# CAN-to-CAN.net
KiCad netlist of a schematic drawn in Altium Designer
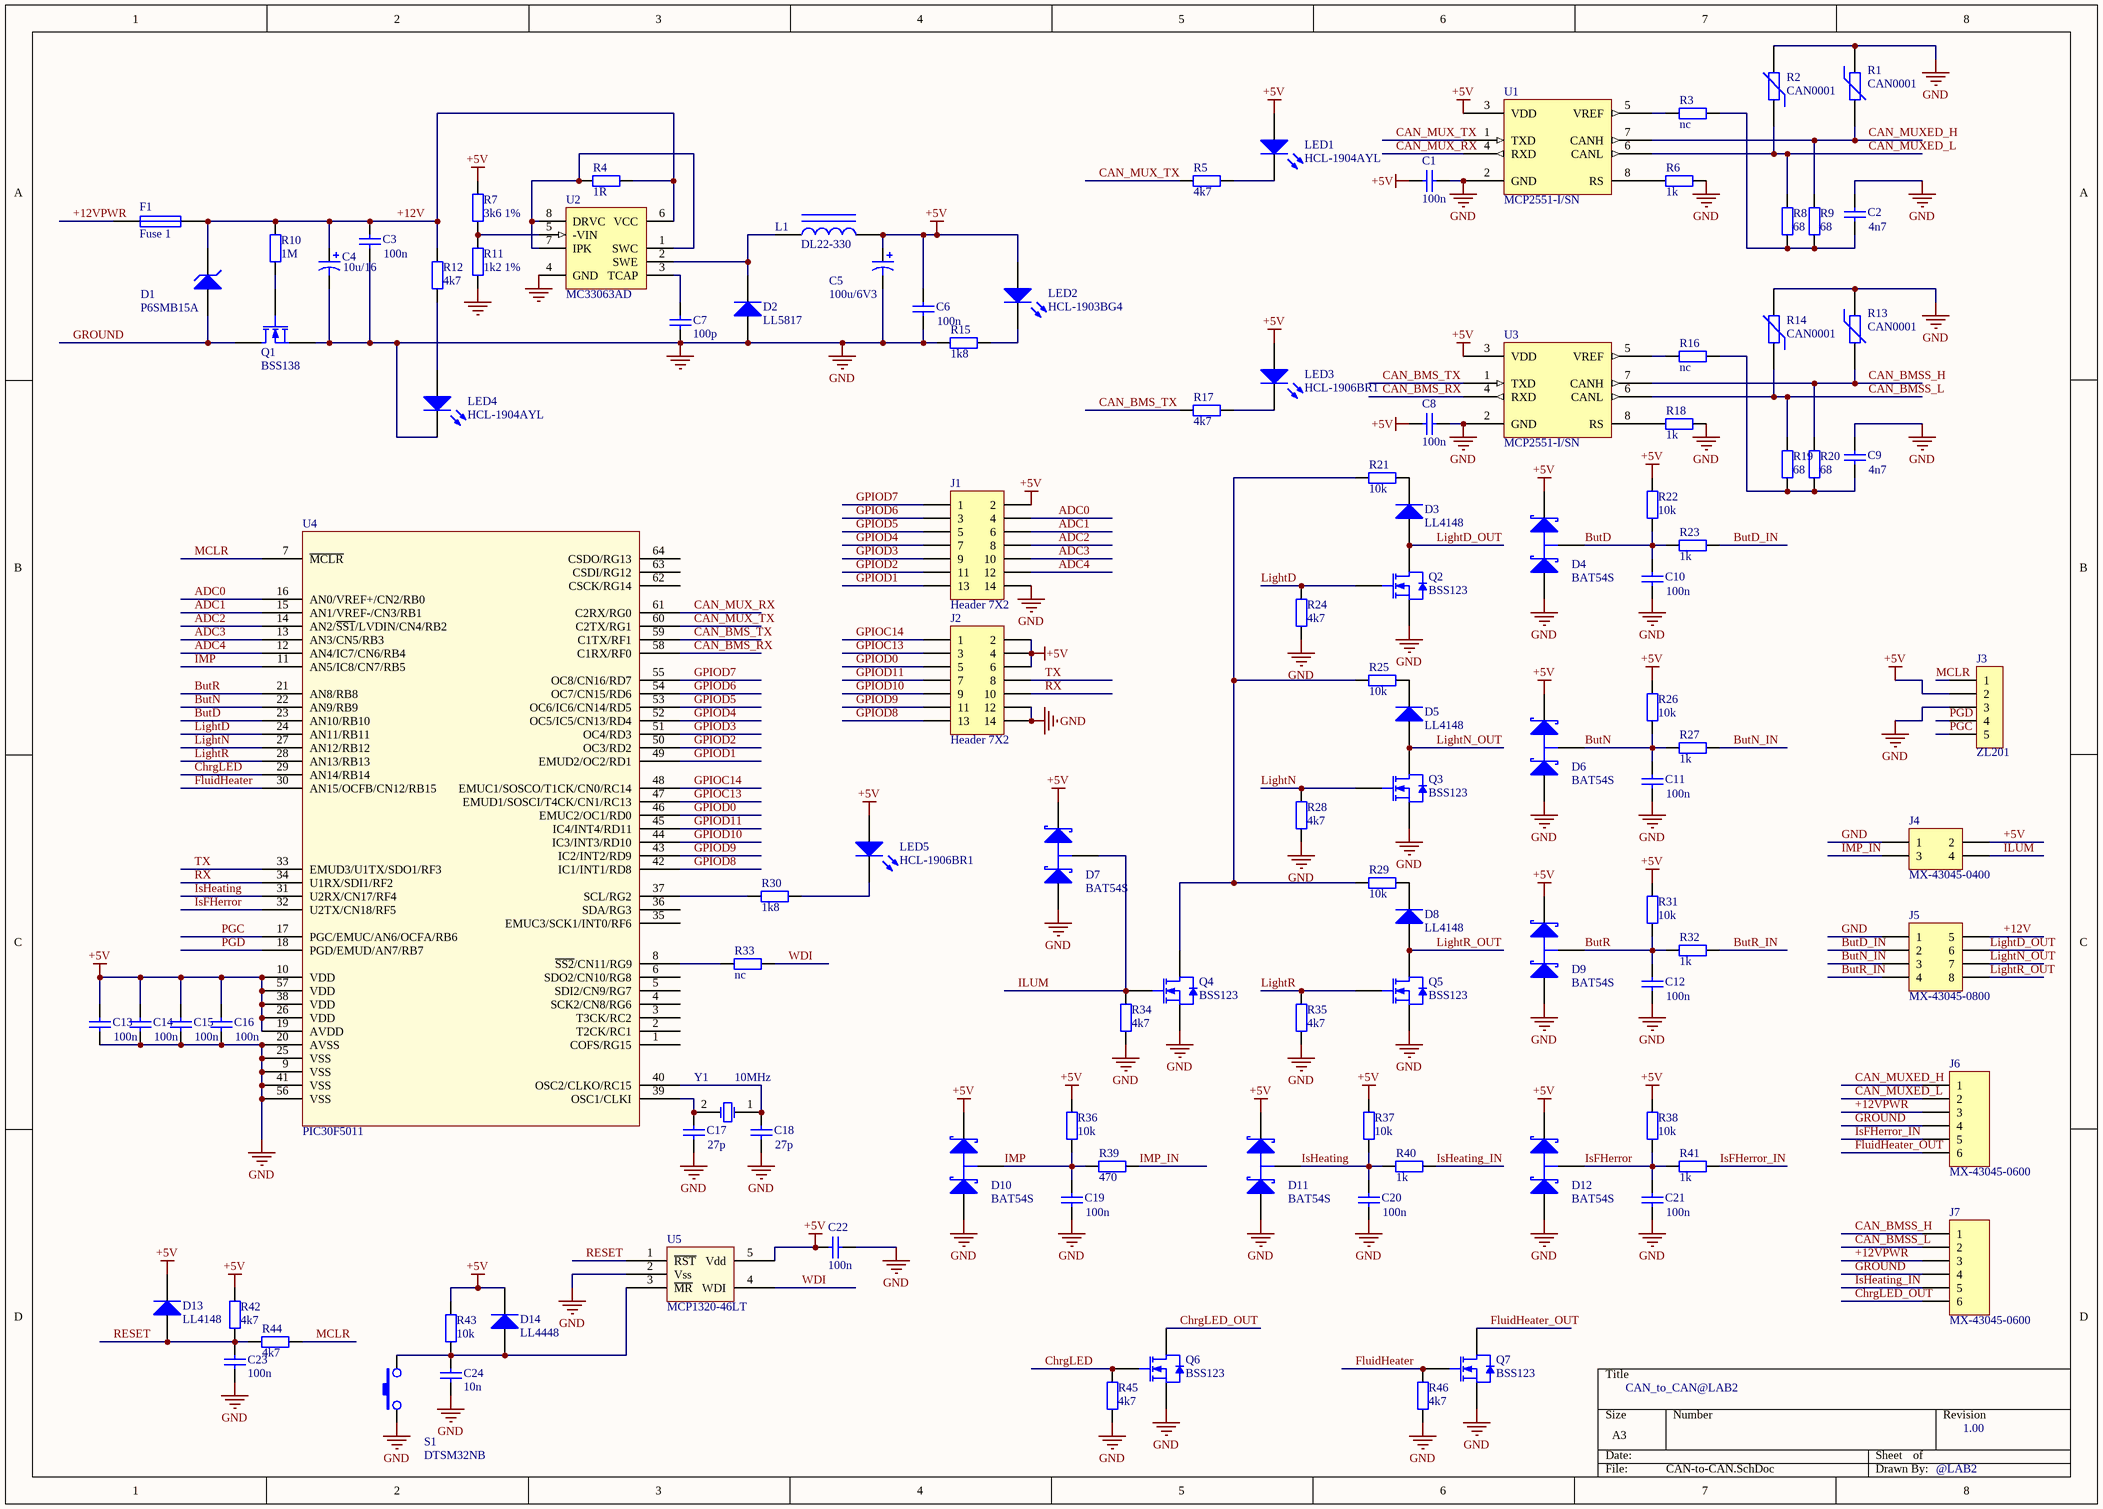
[diagram p0: CAN-to-CAN.SchDoc]

(export (version "E")
  (design (tool "Eeschema 10.0.6"))
  (components
    (comp (ref "C1")
      (value "100n")
      (footprint "0603")
      (description "Capacitor")
      (libsource (lib "Miscellaneous Devices") (part "Cap"))
    )
    (comp (ref "C2")
      (value "4n7")
      (footprint "0603")
      (description "Capacitor")
      (libsource (lib "Miscellaneous Devices") (part "Cap"))
    )
    (comp (ref "C3")
      (value "100n")
      (footprint "3.2X1.6X1.1")
      (description "Capacitor")
      (libsource (lib "Miscellaneous Devices") (part "Cap"))
    )
    (comp (ref "C4")
      (value "10u/16")
      (footprint "1608[0603]")
      (description "Polarized Capacitor (Radial)")
      (libsource (lib "Miscellaneous Devices") (part "Cap Pol1"))
    )
    (comp (ref "C5")
      (value "100u/6V3")
      (footprint "0402")
      (description "Polarized Capacitor (Radial)")
      (libsource (lib "Miscellaneous Devices") (part "Cap Pol1"))
    )
    (comp (ref "C6")
      (value "100n")
      (footprint "0603")
      (description "Capacitor")
      (libsource (lib "Miscellaneous Devices") (part "Cap"))
    )
    (comp (ref "C7")
      (value "100p")
      (footprint "0603")
      (description "Capacitor")
      (libsource (lib "Miscellaneous Devices") (part "Cap"))
    )
    (comp (ref "C8")
      (value "100n")
      (footprint "0603")
      (description "Capacitor")
      (libsource (lib "Miscellaneous Devices") (part "Cap"))
    )
    (comp (ref "C9")
      (value "4n7")
      (footprint "0603")
      (description "Capacitor")
      (libsource (lib "Miscellaneous Devices") (part "Cap"))
    )
    (comp (ref "C10")
      (value "100n")
      (footprint "0603")
      (description "Capacitor")
      (libsource (lib "Miscellaneous Devices") (part "Cap"))
    )
    (comp (ref "C11")
      (value "100n")
      (footprint "0603")
      (description "Capacitor")
      (libsource (lib "Miscellaneous Devices") (part "Cap"))
    )
    (comp (ref "C12")
      (value "100n")
      (footprint "0603")
      (description "Capacitor")
      (libsource (lib "Miscellaneous Devices") (part "Cap"))
    )
    (comp (ref "C13")
      (value "100n")
      (footprint "0603")
      (description "Capacitor")
      (libsource (lib "Miscellaneous Devices") (part "Cap"))
    )
    (comp (ref "C14")
      (value "100n")
      (footprint "0603")
      (description "Capacitor")
      (libsource (lib "Miscellaneous Devices") (part "Cap"))
    )
    (comp (ref "C15")
      (value "100n")
      (footprint "0603")
      (description "Capacitor")
      (libsource (lib "Miscellaneous Devices") (part "Cap"))
    )
    (comp (ref "C16")
      (value "100n")
      (footprint "0603")
      (description "Capacitor")
      (libsource (lib "Miscellaneous Devices") (part "Cap"))
    )
    (comp (ref "C17")
      (value "27p")
      (footprint "0603")
      (description "Capacitor")
      (libsource (lib "Miscellaneous Devices") (part "Cap"))
    )
    (comp (ref "C18")
      (value "27p")
      (footprint "0603")
      (description "Capacitor")
      (libsource (lib "Miscellaneous Devices") (part "Cap"))
    )
    (comp (ref "C19")
      (value "100n")
      (footprint "0603")
      (description "Capacitor")
      (libsource (lib "Miscellaneous Devices") (part "Cap"))
    )
    (comp (ref "C20")
      (value "100n")
      (footprint "0603")
      (description "Capacitor")
      (libsource (lib "Miscellaneous Devices") (part "Cap"))
    )
    (comp (ref "C21")
      (value "100n")
      (footprint "0603")
      (description "Capacitor")
      (libsource (lib "Miscellaneous Devices") (part "Cap"))
    )
    (comp (ref "C22")
      (value "100n")
      (footprint "0603")
      (description "Capacitor")
      (libsource (lib "Miscellaneous Devices") (part "Cap"))
    )
    (comp (ref "C23")
      (value "100n")
      (footprint "0603")
      (description "Capacitor")
      (libsource (lib "Miscellaneous Devices") (part "Cap"))
    )
    (comp (ref "C24")
      (value "10n")
      (footprint "0603")
      (description "Capacitor")
      (libsource (lib "Miscellaneous Devices") (part "Cap"))
    )
    (comp (ref "D1")
      (value "P6SMB15A")
      (footprint "SMB")
      (description "Zener Diode")
      (libsource (lib "Miscellaneous Devices") (part "D Zener"))
    )
    (comp (ref "D2")
      (value "LL5817")
      (footprint "3.2X1.6X1.1")
      (description "High Conductance Fast Diode")
      (libsource (lib "FSC Discrete Diode") (part "1N4148"))
    )
    (comp (ref "D3")
      (value "LL4148")
      (footprint "3.2X1.6X1.1")
      (description "High Conductance Fast Diode")
      (libsource (lib "FSC Discrete Diode") (part "1N4148"))
    )
    (comp (ref "D4")
      (value "BAT54S")
      (footprint "3.2X1.6X1.1")
      (description "Schottky Barrier Double Diode")
      (libsource (lib "Philips Discrete Diode - Schottky") (part "BAT54S"))
    )
    (comp (ref "D5")
      (value "LL4148")
      (footprint "3.2X1.6X1.1")
      (description "High Conductance Fast Diode")
      (libsource (lib "FSC Discrete Diode") (part "1N4148"))
    )
    (comp (ref "D6")
      (value "BAT54S")
      (footprint "3.5X2.8X1.9")
      (description "Schottky Barrier Double Diode")
      (libsource (lib "Philips Discrete Diode - Schottky") (part "BAT54S"))
    )
    (comp (ref "D7")
      (value "BAT54S")
      (footprint "3.2X1.6X1.1")
      (description "Schottky Barrier Double Diode")
      (libsource (lib "Philips Discrete Diode - Schottky") (part "BAT54S"))
    )
    (comp (ref "D8")
      (value "LL4148")
      (footprint "3.2X1.6X1.1")
      (description "High Conductance Fast Diode")
      (libsource (lib "FSC Discrete Diode") (part "1N4148"))
    )
    (comp (ref "D9")
      (value "BAT54S")
      (footprint "3.5X2.8X1.9")
      (description "Schottky Barrier Double Diode")
      (libsource (lib "Philips Discrete Diode - Schottky") (part "BAT54S"))
    )
    (comp (ref "D10")
      (value "BAT54S")
      (footprint "3.2X1.6X1.1")
      (description "Schottky Barrier Double Diode")
      (libsource (lib "Philips Discrete Diode - Schottky") (part "BAT54S"))
    )
    (comp (ref "D11")
      (value "BAT54S")
      (footprint "3.2X1.6X1.1")
      (description "Schottky Barrier Double Diode")
      (libsource (lib "Philips Discrete Diode - Schottky") (part "BAT54S"))
    )
    (comp (ref "D12")
      (value "BAT54S")
      (footprint "3.2X1.6X1.1")
      (description "Schottky Barrier Double Diode")
      (libsource (lib "Philips Discrete Diode - Schottky") (part "BAT54S"))
    )
    (comp (ref "D13")
      (value "LL4148")
      (footprint "3.2X1.6X1.1")
      (description "High Conductance Fast Diode")
      (libsource (lib "FSC Discrete Diode") (part "1N4148"))
    )
    (comp (ref "D14")
      (value "LL4448")
      (footprint "3.2X1.6X1.1")
      (description "Default Diode")
      (libsource (lib "Miscellaneous Devices") (part "Diode"))
    )
    (comp (ref "F1")
      (value "Fuse 1")
      (footprint "1812")
      (description "Fuse")
      (libsource (lib "Miscellaneous Devices") (part "Fuse 1"))
    )
    (comp (ref "J1")
      (value "Header 7X2")
      (footprint "HDR2X7")
      (description "Header, 7-Pin, Dual row")
      (libsource (lib "Miscellaneous Connectors") (part "Header 7X2"))
    )
    (comp (ref "J2")
      (value "Header 7X2")
      (footprint "HDR2X7")
      (description "Header, 7-Pin, Dual row")
      (libsource (lib "Miscellaneous Connectors") (part "Header 7X2"))
    )
    (comp (ref "J3")
      (value "ZL201")
      (footprint "HDR1X5")
      (description "Connector")
      (libsource (lib "*") (part "CON5"))
    )
    (comp (ref "J4")
      (value "MX-43045-0400")
      (footprint "MHDR2X2")
      (description "Header, 2-Pin, Dual row")
      (libsource (lib "Miscellaneous Connectors") (part "Header 2X2"))
    )
    (comp (ref "J5")
      (value "MX-43045-0800")
      (footprint "MHDR2X8")
      (description "Header, 4-Pin, Dual row")
      (libsource (lib "Miscellaneous Connectors") (part "Header 4X2A"))
    )
    (comp (ref "J6")
      (value "MX-43045-0600")
      (footprint "MHDR1X6")
      (description "Header, 6-Pin")
      (libsource (lib "Miscellaneous Connectors") (part "Header 6"))
    )
    (comp (ref "J7")
      (value "MX-43045-0600")
      (footprint "MHDR1X6")
      (description "Header, 6-Pin")
      (libsource (lib "Miscellaneous Connectors") (part "Header 6"))
    )
    (comp (ref "L1")
      (value "DL22-330")
      (footprint "14-1210")
      (description "Magnetic-Core Inductor")
      (libsource (lib "Miscellaneous Devices") (part "Inductor Iron"))
    )
    (comp (ref "LED1")
      (value "HCL-1904AYL")
      (footprint "0603")
      (description "Typical BLUE SiC LED")
      (libsource (lib "Miscellaneous Devices") (part "LED3"))
    )
    (comp (ref "LED2")
      (value "HCL-1903BG4")
      (footprint "0603")
      (description "Typical BLUE SiC LED")
      (libsource (lib "Miscellaneous Devices") (part "LED3"))
    )
    (comp (ref "LED3")
      (value "HCL-1906BR1")
      (footprint "0603")
      (description "Typical BLUE SiC LED")
      (libsource (lib "Miscellaneous Devices") (part "LED3"))
    )
    (comp (ref "LED4")
      (value "HCL-1904AYL")
      (footprint "0603")
      (description "Typical BLUE SiC LED")
      (libsource (lib "Miscellaneous Devices") (part "LED3"))
    )
    (comp (ref "LED5")
      (value "HCL-1906BR1")
      (footprint "0603")
      (description "Typical BLUE SiC LED")
      (libsource (lib "Miscellaneous Devices") (part "LED3"))
    )
    (comp (ref "Q1")
      (value "BSS138")
      (footprint "3.2X1.6X1.1")
      (description "N-Channel Enhancement Mode Vertical DMOS FET")
      (libsource (lib "Zetex Discrete MOSFET") (part "BSS138"))
    )
    (comp (ref "Q2")
      (value "BSS123")
      (footprint "3.2X1.6X1.1")
      (description "N-channel Enhancement Mode Vertical D-MOSFET")
      (libsource (lib "Philips Discrete MOSFET - Low Power") (part "BSS123"))
    )
    (comp (ref "Q3")
      (value "BSS123")
      (footprint "3.2X1.6X1.1")
      (description "N-channel Enhancement Mode Vertical D-MOSFET")
      (libsource (lib "Philips Discrete MOSFET - Low Power") (part "BSS123"))
    )
    (comp (ref "Q4")
      (value "BSS123")
      (footprint "3.5X2.8X1.9")
      (description "N-channel Enhancement Mode Vertical D-MOSFET")
      (libsource (lib "Philips Discrete MOSFET - Low Power") (part "BSS123"))
    )
    (comp (ref "Q5")
      (value "BSS123")
      (footprint "3.5X2.8X1.9")
      (description "N-channel Enhancement Mode Vertical D-MOSFET")
      (libsource (lib "Philips Discrete MOSFET - Low Power") (part "BSS123"))
    )
    (comp (ref "Q6")
      (value "BSS123")
      (footprint "3.2X1.6X1.1")
      (description "N-channel Enhancement Mode Vertical D-MOSFET")
      (libsource (lib "Philips Discrete MOSFET - Low Power") (part "BSS123"))
    )
    (comp (ref "Q7")
      (value "BSS123")
      (footprint "3.5X2.8X1.9")
      (description "N-channel Enhancement Mode Vertical D-MOSFET")
      (libsource (lib "Philips Discrete MOSFET - Low Power") (part "BSS123"))
    )
    (comp (ref "R1")
      (value "CAN0001")
      (footprint "0603")
      (description "Varistor (Voltage-Sensitive Resistor)")
      (libsource (lib "Miscellaneous Devices") (part "Res Varistor"))
    )
    (comp (ref "R2")
      (value "CAN0001")
      (footprint "0603")
      (description "Varistor (Voltage-Sensitive Resistor)")
      (libsource (lib "Miscellaneous Devices") (part "Res Varistor"))
    )
    (comp (ref "R3")
      (value "nc")
      (footprint "0603")
      (description "Resistor")
      (libsource (lib "") (part "Res2_2"))
    )
    (comp (ref "R4")
      (value "1R")
      (footprint "RESC6332")
      (description "Resistor")
      (libsource (lib "") (part "Res2_2"))
    )
    (comp (ref "R5")
      (value "4k7")
      (footprint "0603")
      (description "Resistor")
      (libsource (lib "") (part "Res2_1"))
    )
    (comp (ref "R6")
      (value "1k")
      (footprint "0603")
      (description "Resistor")
      (libsource (lib "") (part "Res2_2"))
    )
    (comp (ref "R7")
      (value "3k6 1%")
      (footprint "0603")
      (description "Resistor")
      (libsource (lib "Miscellaneous Devices") (part "Res2"))
    )
    (comp (ref "R8")
      (value "68")
      (footprint "0603")
      (description "Resistor")
      (libsource (lib "Miscellaneous Devices") (part "Res2"))
    )
    (comp (ref "R9")
      (value "68")
      (footprint "0603")
      (description "Resistor")
      (libsource (lib "Miscellaneous Devices") (part "Res2"))
    )
    (comp (ref "R10")
      (value "1M")
      (footprint "0603")
      (description "Resistor")
      (libsource (lib "Miscellaneous Devices") (part "Res2"))
    )
    (comp (ref "R11")
      (value "1k2 1%")
      (footprint "0603")
      (description "Resistor")
      (libsource (lib "") (part "Res2_3"))
    )
    (comp (ref "R12")
      (value "4k7")
      (footprint "0603")
      (description "Resistor")
      (libsource (lib "Miscellaneous Devices") (part "Res2"))
    )
    (comp (ref "R13")
      (value "CAN0001")
      (footprint "0603")
      (description "Varistor (Voltage-Sensitive Resistor)")
      (libsource (lib "Miscellaneous Devices") (part "Res Varistor"))
    )
    (comp (ref "R14")
      (value "CAN0001")
      (footprint "0603")
      (description "Varistor (Voltage-Sensitive Resistor)")
      (libsource (lib "Miscellaneous Devices") (part "Res Varistor"))
    )
    (comp (ref "R15")
      (value "1k8")
      (footprint "0603")
      (description "Resistor")
      (libsource (lib "") (part "Res2_1"))
    )
    (comp (ref "R16")
      (value "nc")
      (footprint "0603")
      (description "Resistor")
      (libsource (lib "") (part "Res2_2"))
    )
    (comp (ref "R17")
      (value "4k7")
      (footprint "0603")
      (description "Resistor")
      (libsource (lib "") (part "Res2_1"))
    )
    (comp (ref "R18")
      (value "1k")
      (footprint "0603")
      (description "Resistor")
      (libsource (lib "") (part "Res2_2"))
    )
    (comp (ref "R19")
      (value "68")
      (footprint "0603")
      (description "Resistor")
      (libsource (lib "Miscellaneous Devices") (part "Res2"))
    )
    (comp (ref "R20")
      (value "68")
      (footprint "0603")
      (description "Resistor")
      (libsource (lib "Miscellaneous Devices") (part "Res2"))
    )
    (comp (ref "R21")
      (value "10k")
      (footprint "0603")
      (description "Resistor")
      (libsource (lib "") (part "Res2_2"))
    )
    (comp (ref "R22")
      (value "10k")
      (footprint "0603")
      (description "Resistor")
      (libsource (lib "Miscellaneous Devices") (part "Res2"))
    )
    (comp (ref "R23")
      (value "1k")
      (footprint "0603")
      (description "Resistor")
      (libsource (lib "") (part "Res2_1"))
    )
    (comp (ref "R24")
      (value "4k7")
      (footprint "0603")
      (description "Resistor")
      (libsource (lib "Miscellaneous Devices") (part "Res2"))
    )
    (comp (ref "R25")
      (value "10k")
      (footprint "0603")
      (description "Resistor")
      (libsource (lib "") (part "Res2_2"))
    )
    (comp (ref "R26")
      (value "10k")
      (footprint "0603")
      (description "Resistor")
      (libsource (lib "Miscellaneous Devices") (part "Res2"))
    )
    (comp (ref "R27")
      (value "1k")
      (footprint "0603")
      (description "Resistor")
      (libsource (lib "") (part "Res2_1"))
    )
    (comp (ref "R28")
      (value "4k7")
      (footprint "0603")
      (description "Resistor")
      (libsource (lib "Miscellaneous Devices") (part "Res2"))
    )
    (comp (ref "R29")
      (value "10k")
      (footprint "0603")
      (description "Resistor")
      (libsource (lib "") (part "Res2_2"))
    )
    (comp (ref "R30")
      (value "1k8")
      (footprint "0603")
      (description "Resistor")
      (libsource (lib "") (part "Res2_1"))
    )
    (comp (ref "R31")
      (value "10k")
      (footprint "0603")
      (description "Resistor")
      (libsource (lib "Miscellaneous Devices") (part "Res2"))
    )
    (comp (ref "R32")
      (value "1k")
      (footprint "0603")
      (description "Resistor")
      (libsource (lib "") (part "Res2_1"))
    )
    (comp (ref "R33")
      (value "nc")
      (footprint "0603")
      (description "Resistor")
      (libsource (lib "") (part "Res2_1"))
    )
    (comp (ref "R34")
      (value "4k7")
      (footprint "0603")
      (description "Resistor")
      (libsource (lib "Miscellaneous Devices") (part "Res2"))
    )
    (comp (ref "R35")
      (value "4k7")
      (footprint "0603")
      (description "Resistor")
      (libsource (lib "Miscellaneous Devices") (part "Res2"))
    )
    (comp (ref "R36")
      (value "10k")
      (footprint "0603")
      (description "Resistor")
      (libsource (lib "Miscellaneous Devices") (part "Res2"))
    )
    (comp (ref "R37")
      (value "10k")
      (footprint "0603")
      (description "Resistor")
      (libsource (lib "Miscellaneous Devices") (part "Res2"))
    )
    (comp (ref "R38")
      (value "10k")
      (footprint "0603")
      (description "Resistor")
      (libsource (lib "Miscellaneous Devices") (part "Res2"))
    )
    (comp (ref "R39")
      (value "470")
      (footprint "0603")
      (description "Resistor")
      (libsource (lib "") (part "Res2_1"))
    )
    (comp (ref "R40")
      (value "1k")
      (footprint "0603")
      (description "Resistor")
      (libsource (lib "") (part "Res2_1"))
    )
    (comp (ref "R41")
      (value "1k")
      (footprint "0603")
      (description "Resistor")
      (libsource (lib "") (part "Res2_1"))
    )
    (comp (ref "R42")
      (value "4k7")
      (footprint "0603")
      (description "Resistor")
      (libsource (lib "Miscellaneous Devices") (part "Res2"))
    )
    (comp (ref "R43")
      (value "10k")
      (footprint "0603")
      (description "Resistor")
      (libsource (lib "") (part "Res2_3"))
    )
    (comp (ref "R44")
      (value "4k7")
      (footprint "0603")
      (description "Resistor")
      (libsource (lib "") (part "Res2_1"))
    )
    (comp (ref "R45")
      (value "4k7")
      (footprint "0603")
      (description "Resistor")
      (libsource (lib "Miscellaneous Devices") (part "Res2"))
    )
    (comp (ref "R46")
      (value "4k7")
      (footprint "0603")
      (description "Resistor")
      (libsource (lib "Miscellaneous Devices") (part "Res2"))
    )
    (comp (ref "S1")
      (value "DTSM32NB")
      (footprint "3.5X2.8X1.9")
      (description "Switch PushButton")
      (libsource (lib "*") (part "PUSHB"))
    )
    (comp (ref "U1")
      (value "MCP2551-I/SN")
      (footprint "HDR2X8")
      (description "High Speed CAN Transceiver, 8-Pin Plastic SOIC, Industrial Grade")
      (libsource (lib "Microchip Interface Line Transceiver") (part "MCP2551-I/SN"))
    )
    (comp (ref "U2")
      (value "MC33063AD")
      (footprint "SO8_N")
      (description "DC-to-DC Converter Control Circuit")
      (libsource (lib "Motorola Power Mgt DC-DC Converter") (part "MC33063AD"))
    )
    (comp (ref "U3")
      (value "MCP2551-I/SN")
      (footprint "MHDR1X8")
      (description "High Speed CAN Transceiver, 8-Pin Plastic SOIC, Industrial Grade")
      (libsource (lib "Microchip Interface Line Transceiver") (part "MCP2551-I/SN"))
    )
    (comp (ref "U4")
      (value "PIC30F5011")
      (footprint "QFP50P1200X1200X120-64N")
      (description "PIC30F5011 - Up")
      (libsource (lib "X-Tro's Misc") (part "PIC30F5011"))
    )
    (comp (ref "U5")
      (value "MCP1320-46LT")
      (footprint "HDR1X5")
      (libsource (lib "X-Tro's Misc") (part "MCP1320"))
    )
    (comp (ref "Y1")
      (value "10MHz")
      (footprint "3.2X1.6X1.1")
      (description "Crystal Oscillator")
      (libsource (lib "Miscellaneous Devices") (part "XTAL"))
    )
  )
  (nets
    (net (code "1") (name "+5V") (class "Default")
      (node (ref "C1") (pin "1") (pinfunction "1_1") (pintype "passive"))
      (node (ref "C13") (pin "1") (pinfunction "1_1") (pintype "passive"))
      (node (ref "C14") (pin "1") (pinfunction "1_1") (pintype "passive"))
      (node (ref "C15") (pin "1") (pinfunction "1_1") (pintype "passive"))
      (node (ref "C16") (pin "1") (pinfunction "1_1") (pintype "passive"))
      (node (ref "C22") (pin "1") (pinfunction "1_1") (pintype "passive"))
      (node (ref "C5") (pin "1") (pinfunction "1_1") (pintype "passive"))
      (node (ref "C6") (pin "1") (pinfunction "1_1") (pintype "passive"))
      (node (ref "C8") (pin "1") (pinfunction "1_1") (pintype "passive"))
      (node (ref "D10") (pin "2") (pinfunction "K_2") (pintype "passive"))
      (node (ref "D11") (pin "2") (pinfunction "K_2") (pintype "passive"))
      (node (ref "D12") (pin "2") (pinfunction "K_2") (pintype "passive"))
      (node (ref "D13") (pin "2") (pinfunction "K_2") (pintype "passive"))
      (node (ref "D14") (pin "2") (pinfunction "K_2") (pintype "passive"))
      (node (ref "D4") (pin "2") (pinfunction "K_2") (pintype "passive"))
      (node (ref "D6") (pin "2") (pinfunction "K_2") (pintype "passive"))
      (node (ref "D7") (pin "2") (pinfunction "K_2") (pintype "passive"))
      (node (ref "D9") (pin "2") (pinfunction "K_2") (pintype "passive"))
      (node (ref "J1") (pin "2") (pinfunction "2_2") (pintype "passive"))
      (node (ref "J2") (pin "2") (pinfunction "2_2") (pintype "passive"))
      (node (ref "J2") (pin "4") (pinfunction "4_4") (pintype "passive"))
      (node (ref "J2") (pin "6") (pinfunction "6_6") (pintype "passive"))
      (node (ref "J3") (pin "2") (pinfunction "2_2") (pintype "passive"))
      (node (ref "J4") (pin "2") (pinfunction "2_2") (pintype "passive"))
      (node (ref "L1") (pin "2") (pinfunction "2_2") (pintype "passive"))
      (node (ref "LED1") (pin "1") (pinfunction "A_1") (pintype "passive"))
      (node (ref "LED2") (pin "1") (pinfunction "A_1") (pintype "passive"))
      (node (ref "LED3") (pin "1") (pinfunction "A_1") (pintype "passive"))
      (node (ref "LED5") (pin "1") (pinfunction "A_1") (pintype "passive"))
      (node (ref "R22") (pin "1") (pinfunction "1_1") (pintype "passive"))
      (node (ref "R26") (pin "1") (pinfunction "1_1") (pintype "passive"))
      (node (ref "R31") (pin "1") (pinfunction "1_1") (pintype "passive"))
      (node (ref "R36") (pin "1") (pinfunction "1_1") (pintype "passive"))
      (node (ref "R37") (pin "1") (pinfunction "1_1") (pintype "passive"))
      (node (ref "R38") (pin "1") (pinfunction "1_1") (pintype "passive"))
      (node (ref "R42") (pin "1") (pinfunction "1_1") (pintype "passive"))
      (node (ref "R43") (pin "2") (pinfunction "2_2") (pintype "passive"))
      (node (ref "R7") (pin "1") (pinfunction "1_1") (pintype "passive"))
      (node (ref "U1") (pin "3") (pinfunction "VDD_3") (pintype "power_in"))
      (node (ref "U3") (pin "3") (pinfunction "VDD_3") (pintype "power_in"))
      (node (ref "U4") (pin "10") (pinfunction "VDD_10") (pintype "passive"))
      (node (ref "U4") (pin "19") (pinfunction "AVDD_19") (pintype "passive"))
      (node (ref "U4") (pin "26") (pinfunction "VDD_26") (pintype "passive"))
      (node (ref "U4") (pin "38") (pinfunction "VDD_38") (pintype "passive"))
      (node (ref "U4") (pin "57") (pinfunction "VDD_57") (pintype "passive"))
      (node (ref "U5") (pin "5") (pinfunction "Vdd_5") (pintype "passive"))
    )
    (net (code "2") (name "/+12V") (class "Default")
      (node (ref "C3") (pin "1") (pinfunction "1_1") (pintype "passive"))
      (node (ref "C4") (pin "1") (pinfunction "1_1") (pintype "passive"))
      (node (ref "D1") (pin "2") (pinfunction "K_2") (pintype "passive"))
      (node (ref "F1") (pin "2") (pinfunction "2_2") (pintype "passive"))
      (node (ref "J5") (pin "5") (pinfunction "5_5") (pintype "passive"))
      (node (ref "R10") (pin "1") (pinfunction "1_1") (pintype "passive"))
      (node (ref "R12") (pin "1") (pinfunction "1_1") (pintype "passive"))
      (node (ref "R4") (pin "2") (pinfunction "2_2") (pintype "passive"))
      (node (ref "U2") (pin "6") (pinfunction "VCC_6") (pintype "power_in"))
    )
    (net (code "3") (name "/+12VPWR") (class "Default")
      (node (ref "F1") (pin "1") (pinfunction "1_1") (pintype "passive"))
      (node (ref "J6") (pin "3") (pinfunction "3_3") (pintype "passive"))
      (node (ref "J7") (pin "3") (pinfunction "3_3") (pintype "passive"))
    )
    (net (code "4") (name "/ADC0") (class "Default")
      (node (ref "J1") (pin "4") (pinfunction "4_4") (pintype "passive"))
      (node (ref "U4") (pin "16") (pinfunction "AN0/VREF+/CN2/RB0_16") (pintype "passive"))
    )
    (net (code "5") (name "/ADC1") (class "Default")
      (node (ref "J1") (pin "6") (pinfunction "6_6") (pintype "passive"))
      (node (ref "U4") (pin "15") (pinfunction "AN1/VREF-/CN3/RB1_15") (pintype "passive"))
    )
    (net (code "6") (name "/ADC2") (class "Default")
      (node (ref "J1") (pin "8") (pinfunction "8_8") (pintype "passive"))
      (node (ref "U4") (pin "14") (pinfunction "AN2/~{SS1}/LVDIN/CN4/RB2_14") (pintype "passive"))
    )
    (net (code "7") (name "/ADC3") (class "Default")
      (node (ref "J1") (pin "10") (pinfunction "10_10") (pintype "passive"))
      (node (ref "U4") (pin "13") (pinfunction "AN3/CN5/RB3_13") (pintype "passive"))
    )
    (net (code "8") (name "/ADC4") (class "Default")
      (node (ref "J1") (pin "12") (pinfunction "12_12") (pintype "passive"))
      (node (ref "U4") (pin "12") (pinfunction "AN4/IC7/CN6/RB4_12") (pintype "passive"))
    )
    (net (code "9") (name "/ButD") (class "Default")
      (node (ref "C10") (pin "1") (pinfunction "1_1") (pintype "passive"))
      (node (ref "D4") (pin "3") (pinfunction "C_3") (pintype "passive"))
      (node (ref "R22") (pin "2") (pinfunction "2_2") (pintype "passive"))
      (node (ref "R23") (pin "2") (pinfunction "2_2") (pintype "passive"))
      (node (ref "U4") (pin "23") (pinfunction "AN10/RB10_23") (pintype "passive"))
    )
    (net (code "10") (name "/ButD_IN") (class "Default")
      (node (ref "J5") (pin "2") (pinfunction "2_2") (pintype "passive"))
      (node (ref "R23") (pin "1") (pinfunction "1_1") (pintype "passive"))
    )
    (net (code "11") (name "/ButN") (class "Default")
      (node (ref "C11") (pin "1") (pinfunction "1_1") (pintype "passive"))
      (node (ref "D6") (pin "3") (pinfunction "C_3") (pintype "passive"))
      (node (ref "R26") (pin "2") (pinfunction "2_2") (pintype "passive"))
      (node (ref "R27") (pin "2") (pinfunction "2_2") (pintype "passive"))
      (node (ref "U4") (pin "22") (pinfunction "AN9/RB9_22") (pintype "passive"))
    )
    (net (code "12") (name "/ButN_IN") (class "Default")
      (node (ref "J5") (pin "3") (pinfunction "3_3") (pintype "passive"))
      (node (ref "R27") (pin "1") (pinfunction "1_1") (pintype "passive"))
    )
    (net (code "13") (name "/ButR") (class "Default")
      (node (ref "C12") (pin "1") (pinfunction "1_1") (pintype "passive"))
      (node (ref "D9") (pin "3") (pinfunction "C_3") (pintype "passive"))
      (node (ref "R31") (pin "2") (pinfunction "2_2") (pintype "passive"))
      (node (ref "R32") (pin "2") (pinfunction "2_2") (pintype "passive"))
      (node (ref "U4") (pin "21") (pinfunction "AN8/RB8_21") (pintype "passive"))
    )
    (net (code "14") (name "/ButR_IN") (class "Default")
      (node (ref "J5") (pin "4") (pinfunction "4_4") (pintype "passive"))
      (node (ref "R32") (pin "1") (pinfunction "1_1") (pintype "passive"))
    )
    (net (code "15") (name "/CAN_BMSS_H") (class "Default")
      (node (ref "J7") (pin "1") (pinfunction "1_1") (pintype "passive"))
      (node (ref "R13") (pin "2") (pinfunction "2_2") (pintype "passive"))
      (node (ref "R20") (pin "1") (pinfunction "1_1") (pintype "passive"))
      (node (ref "U3") (pin "7") (pinfunction "CANH_7") (pintype "output"))
    )
    (net (code "16") (name "/CAN_BMSS_L") (class "Default")
      (node (ref "J7") (pin "2") (pinfunction "2_2") (pintype "passive"))
      (node (ref "R14") (pin "1") (pinfunction "1_1") (pintype "passive"))
      (node (ref "R19") (pin "1") (pinfunction "1_1") (pintype "passive"))
      (node (ref "U3") (pin "6") (pinfunction "CANL_6") (pintype "output"))
    )
    (net (code "17") (name "/CAN_BMS_RX") (class "Default")
      (node (ref "U3") (pin "4") (pinfunction "RXD_4") (pintype "output"))
      (node (ref "U4") (pin "58") (pinfunction "C1RX/RF0_58") (pintype "passive"))
    )
    (net (code "18") (name "/CAN_BMS_TX") (class "Default")
      (node (ref "R17") (pin "2") (pinfunction "2_2") (pintype "passive"))
      (node (ref "U3") (pin "1") (pinfunction "TXD_1") (pintype "input"))
      (node (ref "U4") (pin "59") (pinfunction "C1TX/RF1_59") (pintype "passive"))
    )
    (net (code "19") (name "/CAN_MUXED_H") (class "Default")
      (node (ref "J6") (pin "1") (pinfunction "1_1") (pintype "passive"))
      (node (ref "R1") (pin "2") (pinfunction "2_2") (pintype "passive"))
      (node (ref "R9") (pin "1") (pinfunction "1_1") (pintype "passive"))
      (node (ref "U1") (pin "7") (pinfunction "CANH_7") (pintype "output"))
    )
    (net (code "20") (name "/CAN_MUXED_L") (class "Default")
      (node (ref "J6") (pin "2") (pinfunction "2_2") (pintype "passive"))
      (node (ref "R2") (pin "1") (pinfunction "1_1") (pintype "passive"))
      (node (ref "R8") (pin "1") (pinfunction "1_1") (pintype "passive"))
      (node (ref "U1") (pin "6") (pinfunction "CANL_6") (pintype "output"))
    )
    (net (code "21") (name "/CAN_MUX_RX") (class "Default")
      (node (ref "U1") (pin "4") (pinfunction "RXD_4") (pintype "output"))
      (node (ref "U4") (pin "61") (pinfunction "C2RX/RG0_61") (pintype "passive"))
    )
    (net (code "22") (name "/CAN_MUX_TX") (class "Default")
      (node (ref "R5") (pin "2") (pinfunction "2_2") (pintype "passive"))
      (node (ref "U1") (pin "1") (pinfunction "TXD_1") (pintype "input"))
      (node (ref "U4") (pin "60") (pinfunction "C2TX/RG1_60") (pintype "passive"))
    )
    (net (code "23") (name "/ChrgLED") (class "Default")
      (node (ref "Q6") (pin "3") (pinfunction "G_3") (pintype "passive"))
      (node (ref "R45") (pin "1") (pinfunction "1_1") (pintype "passive"))
      (node (ref "U4") (pin "29") (pinfunction "AN14/RB14_29") (pintype "passive"))
    )
    (net (code "24") (name "/ChrgLED_OUT") (class "Default")
      (node (ref "J7") (pin "6") (pinfunction "6_6") (pintype "passive"))
      (node (ref "Q6") (pin "1") (pinfunction "D_1") (pintype "passive"))
    )
    (net (code "25") (name "/FluidHeater") (class "Default")
      (node (ref "Q7") (pin "3") (pinfunction "G_3") (pintype "passive"))
      (node (ref "R46") (pin "1") (pinfunction "1_1") (pintype "passive"))
      (node (ref "U4") (pin "30") (pinfunction "AN15/OCFB/CN12/RB15_30") (pintype "passive"))
    )
    (net (code "26") (name "/FluidHeater_OUT") (class "Default")
      (node (ref "J6") (pin "6") (pinfunction "6_6") (pintype "passive"))
      (node (ref "Q7") (pin "1") (pinfunction "D_1") (pintype "passive"))
    )
    (net (code "27") (name "/GPIOC13") (class "Default")
      (node (ref "J2") (pin "3") (pinfunction "3_3") (pintype "passive"))
      (node (ref "U4") (pin "47") (pinfunction "EMUD1/SOSCI/T4CK/CN1/RC13_47") (pintype "passive"))
    )
    (net (code "28") (name "/GPIOC14") (class "Default")
      (node (ref "J2") (pin "1") (pinfunction "1_1") (pintype "passive"))
      (node (ref "U4") (pin "48") (pinfunction "EMUC1/SOSCO/T1CK/CN0/RC14_48") (pintype "passive"))
    )
    (net (code "29") (name "/GPIOD0") (class "Default")
      (node (ref "J2") (pin "5") (pinfunction "5_5") (pintype "passive"))
      (node (ref "U4") (pin "46") (pinfunction "EMUC2/OC1/RD0_46") (pintype "passive"))
    )
    (net (code "30") (name "/GPIOD1") (class "Default")
      (node (ref "J1") (pin "13") (pinfunction "13_13") (pintype "passive"))
      (node (ref "U4") (pin "49") (pinfunction "EMUD2/OC2/RD1_49") (pintype "passive"))
    )
    (net (code "31") (name "/GPIOD2") (class "Default")
      (node (ref "J1") (pin "11") (pinfunction "11_11") (pintype "passive"))
      (node (ref "U4") (pin "50") (pinfunction "OC3/RD2_50") (pintype "passive"))
    )
    (net (code "32") (name "/GPIOD3") (class "Default")
      (node (ref "J1") (pin "9") (pinfunction "9_9") (pintype "passive"))
      (node (ref "U4") (pin "51") (pinfunction "OC4/RD3_51") (pintype "passive"))
    )
    (net (code "33") (name "/GPIOD4") (class "Default")
      (node (ref "J1") (pin "7") (pinfunction "7_7") (pintype "passive"))
      (node (ref "U4") (pin "52") (pinfunction "OC5/IC5/CN13/RD4_52") (pintype "passive"))
    )
    (net (code "34") (name "/GPIOD5") (class "Default")
      (node (ref "J1") (pin "5") (pinfunction "5_5") (pintype "passive"))
      (node (ref "U4") (pin "53") (pinfunction "OC6/IC6/CN14/RD5_53") (pintype "passive"))
    )
    (net (code "35") (name "/GPIOD6") (class "Default")
      (node (ref "J1") (pin "3") (pinfunction "3_3") (pintype "passive"))
      (node (ref "U4") (pin "54") (pinfunction "OC7/CN15/RD6_54") (pintype "passive"))
    )
    (net (code "36") (name "/GPIOD7") (class "Default")
      (node (ref "J1") (pin "1") (pinfunction "1_1") (pintype "passive"))
      (node (ref "U4") (pin "55") (pinfunction "OC8/CN16/RD7_55") (pintype "passive"))
    )
    (net (code "37") (name "/GPIOD8") (class "Default")
      (node (ref "J2") (pin "13") (pinfunction "13_13") (pintype "passive"))
      (node (ref "U4") (pin "42") (pinfunction "IC1/INT1/RD8_42") (pintype "passive"))
    )
    (net (code "38") (name "/GPIOD9") (class "Default")
      (node (ref "J2") (pin "11") (pinfunction "11_11") (pintype "passive"))
      (node (ref "U4") (pin "43") (pinfunction "IC2/INT2/RD9_43") (pintype "passive"))
    )
    (net (code "39") (name "/GPIOD10") (class "Default")
      (node (ref "J2") (pin "9") (pinfunction "9_9") (pintype "passive"))
      (node (ref "U4") (pin "44") (pinfunction "IC3/INT3/RD10_44") (pintype "passive"))
    )
    (net (code "40") (name "/GPIOD11") (class "Default")
      (node (ref "J2") (pin "7") (pinfunction "7_7") (pintype "passive"))
      (node (ref "U4") (pin "45") (pinfunction "IC4/INT4/RD11_45") (pintype "passive"))
    )
    (net (code "41") (name "/GROUND") (class "Default")
      (node (ref "D1") (pin "1") (pinfunction "A_1") (pintype "passive"))
      (node (ref "J6") (pin "4") (pinfunction "4_4") (pintype "passive"))
      (node (ref "J7") (pin "4") (pinfunction "4_4") (pintype "passive"))
      (node (ref "Q1") (pin "1") (pinfunction "D_1") (pintype "passive"))
    )
    (net (code "42") (name "/ILUM") (class "Default")
      (node (ref "D7") (pin "3") (pinfunction "C_3") (pintype "passive"))
      (node (ref "J4") (pin "4") (pinfunction "4_4") (pintype "passive"))
      (node (ref "Q4") (pin "3") (pinfunction "G_3") (pintype "passive"))
      (node (ref "R34") (pin "1") (pinfunction "1_1") (pintype "passive"))
    )
    (net (code "43") (name "/IMP") (class "Default")
      (node (ref "C19") (pin "1") (pinfunction "1_1") (pintype "passive"))
      (node (ref "D10") (pin "3") (pinfunction "C_3") (pintype "passive"))
      (node (ref "R36") (pin "2") (pinfunction "2_2") (pintype "passive"))
      (node (ref "R39") (pin "2") (pinfunction "2_2") (pintype "passive"))
      (node (ref "U4") (pin "11") (pinfunction "AN5/IC8/CN7/RB5_11") (pintype "passive"))
    )
    (net (code "44") (name "/IMP_IN") (class "Default")
      (node (ref "J4") (pin "3") (pinfunction "3_3") (pintype "passive"))
      (node (ref "R39") (pin "1") (pinfunction "1_1") (pintype "passive"))
    )
    (net (code "45") (name "/IsFHerror") (class "Default")
      (node (ref "C21") (pin "1") (pinfunction "1_1") (pintype "passive"))
      (node (ref "D12") (pin "3") (pinfunction "C_3") (pintype "passive"))
      (node (ref "R38") (pin "2") (pinfunction "2_2") (pintype "passive"))
      (node (ref "R41") (pin "2") (pinfunction "2_2") (pintype "passive"))
      (node (ref "U4") (pin "32") (pinfunction "U2TX/CN18/RF5_32") (pintype "passive"))
    )
    (net (code "46") (name "/IsFHerror_IN") (class "Default")
      (node (ref "J6") (pin "5") (pinfunction "5_5") (pintype "passive"))
      (node (ref "R41") (pin "1") (pinfunction "1_1") (pintype "passive"))
    )
    (net (code "47") (name "/IsHeating") (class "Default")
      (node (ref "C20") (pin "1") (pinfunction "1_1") (pintype "passive"))
      (node (ref "D11") (pin "3") (pinfunction "C_3") (pintype "passive"))
      (node (ref "R37") (pin "2") (pinfunction "2_2") (pintype "passive"))
      (node (ref "R40") (pin "2") (pinfunction "2_2") (pintype "passive"))
      (node (ref "U4") (pin "31") (pinfunction "U2RX/CN17/RF4_31") (pintype "passive"))
    )
    (net (code "48") (name "/IsHeating_IN") (class "Default")
      (node (ref "J7") (pin "5") (pinfunction "5_5") (pintype "passive"))
      (node (ref "R40") (pin "1") (pinfunction "1_1") (pintype "passive"))
    )
    (net (code "49") (name "/LightD") (class "Default")
      (node (ref "Q2") (pin "3") (pinfunction "G_3") (pintype "passive"))
      (node (ref "R24") (pin "1") (pinfunction "1_1") (pintype "passive"))
      (node (ref "U4") (pin "24") (pinfunction "AN11/RB11_24") (pintype "passive"))
    )
    (net (code "50") (name "/LightD_OUT") (class "Default")
      (node (ref "D3") (pin "1") (pinfunction "A_1") (pintype "passive"))
      (node (ref "J5") (pin "6") (pinfunction "6_6") (pintype "passive"))
      (node (ref "Q2") (pin "1") (pinfunction "D_1") (pintype "passive"))
    )
    (net (code "51") (name "/LightN") (class "Default")
      (node (ref "Q3") (pin "3") (pinfunction "G_3") (pintype "passive"))
      (node (ref "R28") (pin "1") (pinfunction "1_1") (pintype "passive"))
      (node (ref "U4") (pin "27") (pinfunction "AN12/RB12_27") (pintype "passive"))
    )
    (net (code "52") (name "/LightN_OUT") (class "Default")
      (node (ref "D5") (pin "1") (pinfunction "A_1") (pintype "passive"))
      (node (ref "J5") (pin "7") (pinfunction "7_7") (pintype "passive"))
      (node (ref "Q3") (pin "1") (pinfunction "D_1") (pintype "passive"))
    )
    (net (code "53") (name "/LightR") (class "Default")
      (node (ref "Q5") (pin "3") (pinfunction "G_3") (pintype "passive"))
      (node (ref "R35") (pin "1") (pinfunction "1_1") (pintype "passive"))
      (node (ref "U4") (pin "28") (pinfunction "AN13/RB13_28") (pintype "passive"))
    )
    (net (code "54") (name "/LightR_OUT") (class "Default")
      (node (ref "D8") (pin "1") (pinfunction "A_1") (pintype "passive"))
      (node (ref "J5") (pin "8") (pinfunction "8_8") (pintype "passive"))
      (node (ref "Q5") (pin "1") (pinfunction "D_1") (pintype "passive"))
    )
    (net (code "55") (name "/MCLR") (class "Default")
      (node (ref "J3") (pin "1") (pinfunction "1_1") (pintype "passive"))
      (node (ref "R44") (pin "1") (pinfunction "1_1") (pintype "passive"))
      (node (ref "U4") (pin "7") (pinfunction "~{MCLR}_7") (pintype "passive"))
    )
    (net (code "56") (name "/PGC") (class "Default")
      (node (ref "J3") (pin "5") (pinfunction "5_5") (pintype "passive"))
      (node (ref "U4") (pin "17") (pinfunction "PGC/EMUC/AN6/OCFA/RB6_17") (pintype "passive"))
    )
    (net (code "57") (name "/PGD") (class "Default")
      (node (ref "J3") (pin "4") (pinfunction "4_4") (pintype "passive"))
      (node (ref "U4") (pin "18") (pinfunction "PGD/EMUD/AN7/RB7_18") (pintype "passive"))
    )
    (net (code "58") (name "/RESET") (class "Default")
      (node (ref "C23") (pin "2") (pinfunction "2_2") (pintype "passive"))
      (node (ref "D13") (pin "1") (pinfunction "A_1") (pintype "passive"))
      (node (ref "R42") (pin "2") (pinfunction "2_2") (pintype "passive"))
      (node (ref "R44") (pin "2") (pinfunction "2_2") (pintype "passive"))
      (node (ref "U5") (pin "1") (pinfunction "~{RST}_1") (pintype "passive"))
    )
    (net (code "59") (name "/RX") (class "Default")
      (node (ref "J2") (pin "10") (pinfunction "10_10") (pintype "passive"))
      (node (ref "U4") (pin "34") (pinfunction "U1RX/SDI1/RF2_34") (pintype "passive"))
    )
    (net (code "60") (name "/TX") (class "Default")
      (node (ref "J2") (pin "8") (pinfunction "8_8") (pintype "passive"))
      (node (ref "U4") (pin "33") (pinfunction "EMUD3/U1TX/SDO1/RF3_33") (pintype "passive"))
    )
    (net (code "61") (name "/WDI") (class "Default")
      (node (ref "R33") (pin "1") (pinfunction "1_1") (pintype "passive"))
      (node (ref "U5") (pin "4") (pinfunction "WDI_4") (pintype "passive"))
    )
    (net (code "62") (name "GND") (class "Default")
      (node (ref "C1") (pin "2") (pinfunction "2_2") (pintype "passive"))
      (node (ref "C10") (pin "2") (pinfunction "2_2") (pintype "passive"))
      (node (ref "C11") (pin "2") (pinfunction "2_2") (pintype "passive"))
      (node (ref "C12") (pin "2") (pinfunction "2_2") (pintype "passive"))
      (node (ref "C13") (pin "2") (pinfunction "2_2") (pintype "passive"))
      (node (ref "C14") (pin "2") (pinfunction "2_2") (pintype "passive"))
      (node (ref "C15") (pin "2") (pinfunction "2_2") (pintype "passive"))
      (node (ref "C16") (pin "2") (pinfunction "2_2") (pintype "passive"))
      (node (ref "C17") (pin "2") (pinfunction "2_2") (pintype "passive"))
      (node (ref "C18") (pin "2") (pinfunction "2_2") (pintype "passive"))
      (node (ref "C19") (pin "2") (pinfunction "2_2") (pintype "passive"))
      (node (ref "C2") (pin "1") (pinfunction "1_1") (pintype "passive"))
      (node (ref "C20") (pin "2") (pinfunction "2_2") (pintype "passive"))
      (node (ref "C21") (pin "2") (pinfunction "2_2") (pintype "passive"))
      (node (ref "C22") (pin "2") (pinfunction "2_2") (pintype "passive"))
      (node (ref "C23") (pin "1") (pinfunction "1_1") (pintype "passive"))
      (node (ref "C24") (pin "1") (pinfunction "1_1") (pintype "passive"))
      (node (ref "C3") (pin "2") (pinfunction "2_2") (pintype "passive"))
      (node (ref "C4") (pin "2") (pinfunction "2_2") (pintype "passive"))
      (node (ref "C5") (pin "2") (pinfunction "2_2") (pintype "passive"))
      (node (ref "C6") (pin "2") (pinfunction "2_2") (pintype "passive"))
      (node (ref "C7") (pin "1") (pinfunction "1_1") (pintype "passive"))
      (node (ref "C8") (pin "2") (pinfunction "2_2") (pintype "passive"))
      (node (ref "C9") (pin "1") (pinfunction "1_1") (pintype "passive"))
      (node (ref "D10") (pin "1") (pinfunction "A_1") (pintype "passive"))
      (node (ref "D11") (pin "1") (pinfunction "A_1") (pintype "passive"))
      (node (ref "D12") (pin "1") (pinfunction "A_1") (pintype "passive"))
      (node (ref "D2") (pin "1") (pinfunction "A_1") (pintype "passive"))
      (node (ref "D4") (pin "1") (pinfunction "A_1") (pintype "passive"))
      (node (ref "D6") (pin "1") (pinfunction "A_1") (pintype "passive"))
      (node (ref "D7") (pin "1") (pinfunction "A_1") (pintype "passive"))
      (node (ref "D9") (pin "1") (pinfunction "A_1") (pintype "passive"))
      (node (ref "J1") (pin "14") (pinfunction "14_14") (pintype "passive"))
      (node (ref "J2") (pin "12") (pinfunction "12_12") (pintype "passive"))
      (node (ref "J2") (pin "14") (pinfunction "14_14") (pintype "passive"))
      (node (ref "J3") (pin "3") (pinfunction "3_3") (pintype "passive"))
      (node (ref "J4") (pin "1") (pinfunction "1_1") (pintype "passive"))
      (node (ref "J5") (pin "1") (pinfunction "1_1") (pintype "passive"))
      (node (ref "LED4") (pin "2") (pinfunction "K_2") (pintype "passive"))
      (node (ref "Q1") (pin "2") (pinfunction "S_2") (pintype "passive"))
      (node (ref "Q2") (pin "2") (pinfunction "S_2") (pintype "passive"))
      (node (ref "Q3") (pin "2") (pinfunction "S_2") (pintype "passive"))
      (node (ref "Q4") (pin "2") (pinfunction "S_2") (pintype "passive"))
      (node (ref "Q5") (pin "2") (pinfunction "S_2") (pintype "passive"))
      (node (ref "Q6") (pin "2") (pinfunction "S_2") (pintype "passive"))
      (node (ref "Q7") (pin "2") (pinfunction "S_2") (pintype "passive"))
      (node (ref "R1") (pin "1") (pinfunction "1_1") (pintype "passive"))
      (node (ref "R11") (pin "1") (pinfunction "1_1") (pintype "passive"))
      (node (ref "R13") (pin "1") (pinfunction "1_1") (pintype "passive"))
      (node (ref "R14") (pin "2") (pinfunction "2_2") (pintype "passive"))
      (node (ref "R15") (pin "2") (pinfunction "2_2") (pintype "passive"))
      (node (ref "R18") (pin "2") (pinfunction "2_2") (pintype "passive"))
      (node (ref "R2") (pin "2") (pinfunction "2_2") (pintype "passive"))
      (node (ref "R24") (pin "2") (pinfunction "2_2") (pintype "passive"))
      (node (ref "R28") (pin "2") (pinfunction "2_2") (pintype "passive"))
      (node (ref "R34") (pin "2") (pinfunction "2_2") (pintype "passive"))
      (node (ref "R35") (pin "2") (pinfunction "2_2") (pintype "passive"))
      (node (ref "R45") (pin "2") (pinfunction "2_2") (pintype "passive"))
      (node (ref "R46") (pin "2") (pinfunction "2_2") (pintype "passive"))
      (node (ref "R6") (pin "2") (pinfunction "2_2") (pintype "passive"))
      (node (ref "S1") (pin "1") (pintype "passive"))
      (node (ref "U1") (pin "2") (pinfunction "GND_2") (pintype "power_in"))
      (node (ref "U2") (pin "4") (pinfunction "GND_4") (pintype "power_in"))
      (node (ref "U3") (pin "2") (pinfunction "GND_2") (pintype "power_in"))
      (node (ref "U4") (pin "20") (pinfunction "AVSS_20") (pintype "passive"))
      (node (ref "U4") (pin "25") (pinfunction "VSS_25") (pintype "passive"))
      (node (ref "U4") (pin "41") (pinfunction "VSS_41") (pintype "passive"))
      (node (ref "U4") (pin "56") (pinfunction "VSS_56") (pintype "passive"))
      (node (ref "U4") (pin "9") (pinfunction "VSS_9") (pintype "passive"))
      (node (ref "U5") (pin "2") (pinfunction "Vss_2") (pintype "passive"))
    )
    (net (code "63") (name "Net-(C2-Pad2)") (class "Default")
      (node (ref "C2") (pin "2") (pinfunction "2_2") (pintype "passive"))
      (node (ref "R3") (pin "2") (pinfunction "2_2") (pintype "passive"))
      (node (ref "R8") (pin "2") (pinfunction "2_2") (pintype "passive"))
      (node (ref "R9") (pin "2") (pinfunction "2_2") (pintype "passive"))
    )
    (net (code "64") (name "Net-(C9-Pad2)") (class "Default")
      (node (ref "C9") (pin "2") (pinfunction "2_2") (pintype "passive"))
      (node (ref "R16") (pin "2") (pinfunction "2_2") (pintype "passive"))
      (node (ref "R19") (pin "2") (pinfunction "2_2") (pintype "passive"))
      (node (ref "R20") (pin "2") (pinfunction "2_2") (pintype "passive"))
    )
    (net (code "65") (name "Net-(D2-K)") (class "Default")
      (node (ref "D2") (pin "2") (pinfunction "K_2") (pintype "passive"))
      (node (ref "L1") (pin "1") (pinfunction "1_1") (pintype "passive"))
      (node (ref "U2") (pin "2") (pinfunction "SWE_2") (pintype "open_emitter"))
    )
    (net (code "66") (name "Net-(D3-K)") (class "Default")
      (node (ref "D3") (pin "2") (pinfunction "K_2") (pintype "passive"))
      (node (ref "R21") (pin "2") (pinfunction "2_2") (pintype "passive"))
    )
    (net (code "67") (name "Net-(D5-K)") (class "Default")
      (node (ref "D5") (pin "2") (pinfunction "K_2") (pintype "passive"))
      (node (ref "R25") (pin "2") (pinfunction "2_2") (pintype "passive"))
    )
    (net (code "68") (name "Net-(D8-K)") (class "Default")
      (node (ref "D8") (pin "2") (pinfunction "K_2") (pintype "passive"))
      (node (ref "R29") (pin "2") (pinfunction "2_2") (pintype "passive"))
    )
    (net (code "69") (name "Net-(D14-A)") (class "Default")
      (node (ref "C24") (pin "2") (pinfunction "2_2") (pintype "passive"))
      (node (ref "D14") (pin "1") (pinfunction "A_1") (pintype "passive"))
      (node (ref "R43") (pin "1") (pinfunction "1_1") (pintype "passive"))
      (node (ref "S1") (pin "2") (pintype "passive"))
      (node (ref "U5") (pin "3") (pinfunction "~{MR}_3") (pintype "passive"))
    )
    (net (code "70") (name "Net-(LED1-K)") (class "Default")
      (node (ref "LED1") (pin "2") (pinfunction "K_2") (pintype "passive"))
      (node (ref "R5") (pin "1") (pinfunction "1_1") (pintype "passive"))
    )
    (net (code "71") (name "Net-(LED2-K)") (class "Default")
      (node (ref "LED2") (pin "2") (pinfunction "K_2") (pintype "passive"))
      (node (ref "R15") (pin "1") (pinfunction "1_1") (pintype "passive"))
    )
    (net (code "72") (name "Net-(LED3-K)") (class "Default")
      (node (ref "LED3") (pin "2") (pinfunction "K_2") (pintype "passive"))
      (node (ref "R17") (pin "1") (pinfunction "1_1") (pintype "passive"))
    )
    (net (code "73") (name "Net-(LED4-A)") (class "Default")
      (node (ref "LED4") (pin "1") (pinfunction "A_1") (pintype "passive"))
      (node (ref "R12") (pin "2") (pinfunction "2_2") (pintype "passive"))
    )
    (net (code "74") (name "Net-(LED5-K)") (class "Default")
      (node (ref "LED5") (pin "2") (pinfunction "K_2") (pintype "passive"))
      (node (ref "R30") (pin "1") (pinfunction "1_1") (pintype "passive"))
    )
    (net (code "75") (name "Net-(Q1-G)") (class "Default")
      (node (ref "Q1") (pin "3") (pinfunction "G_3") (pintype "passive"))
      (node (ref "R10") (pin "2") (pinfunction "2_2") (pintype "passive"))
    )
    (net (code "76") (name "Net-(Q4-D)") (class "Default")
      (node (ref "Q4") (pin "1") (pinfunction "D_1") (pintype "passive"))
      (node (ref "R21") (pin "1") (pinfunction "1_1") (pintype "passive"))
      (node (ref "R25") (pin "1") (pinfunction "1_1") (pintype "passive"))
      (node (ref "R29") (pin "1") (pinfunction "1_1") (pintype "passive"))
    )
    (net (code "77") (name "Net-(U1-RS)") (class "Default")
      (node (ref "R6") (pin "1") (pinfunction "1_1") (pintype "passive"))
      (node (ref "U1") (pin "8") (pinfunction "RS_8") (pintype "passive"))
    )
    (net (code "78") (name "Net-(U1-VREF)") (class "Default")
      (node (ref "R3") (pin "1") (pinfunction "1_1") (pintype "passive"))
      (node (ref "U1") (pin "5") (pinfunction "VREF_5") (pintype "output"))
    )
    (net (code "79") (name "Net-(U2--VIN)") (class "Default")
      (node (ref "R11") (pin "2") (pinfunction "2_2") (pintype "passive"))
      (node (ref "R7") (pin "2") (pinfunction "2_2") (pintype "passive"))
      (node (ref "U2") (pin "5") (pinfunction "-VIN_5") (pintype "input"))
    )
    (net (code "80") (name "Net-(U2-DRVC)") (class "Default")
      (node (ref "R4") (pin "1") (pinfunction "1_1") (pintype "passive"))
      (node (ref "U2") (pin "1") (pinfunction "SWC_1") (pintype "open_collector"))
      (node (ref "U2") (pin "7") (pinfunction "IPK_7") (pintype "passive"))
      (node (ref "U2") (pin "8") (pinfunction "DRVC_8") (pintype "open_collector"))
    )
    (net (code "81") (name "Net-(U2-TCAP)") (class "Default")
      (node (ref "C7") (pin "2") (pinfunction "2_2") (pintype "passive"))
      (node (ref "U2") (pin "3") (pinfunction "TCAP_3") (pintype "passive"))
    )
    (net (code "82") (name "Net-(U3-RS)") (class "Default")
      (node (ref "R18") (pin "1") (pinfunction "1_1") (pintype "passive"))
      (node (ref "U3") (pin "8") (pinfunction "RS_8") (pintype "passive"))
    )
    (net (code "83") (name "Net-(U3-VREF)") (class "Default")
      (node (ref "R16") (pin "1") (pinfunction "1_1") (pintype "passive"))
      (node (ref "U3") (pin "5") (pinfunction "VREF_5") (pintype "output"))
    )
    (net (code "84") (name "Net-(U4-OSC1{slash}CLKI)") (class "Default")
      (node (ref "C17") (pin "1") (pinfunction "1_1") (pintype "passive"))
      (node (ref "U4") (pin "39") (pinfunction "OSC1/CLKI_39") (pintype "passive"))
      (node (ref "Y1") (pin "2") (pinfunction "OSC2_2") (pintype "passive"))
    )
    (net (code "85") (name "Net-(U4-OSC2{slash}CLKO{slash}RC15)") (class "Default")
      (node (ref "C18") (pin "1") (pinfunction "1_1") (pintype "passive"))
      (node (ref "U4") (pin "40") (pinfunction "OSC2/CLKO/RC15_40") (pintype "passive"))
      (node (ref "Y1") (pin "1") (pinfunction "OSC1_1") (pintype "passive"))
    )
    (net (code "86") (name "Net-(U4-SCL{slash}RG2)") (class "Default")
      (node (ref "R30") (pin "2") (pinfunction "2_2") (pintype "passive"))
      (node (ref "U4") (pin "37") (pinfunction "SCL/RG2_37") (pintype "passive"))
    )
    (net (code "87") (name "Net-(U4-~{SS2}{slash}CN11{slash}RG9)") (class "Default")
      (node (ref "R33") (pin "2") (pinfunction "2_2") (pintype "passive"))
      (node (ref "U4") (pin "8") (pinfunction "~{SS2}/CN11/RG9_8") (pintype "passive"))
    )
    (net (code "88") (name "unconnected-(U4-COFS{slash}RG15-Pad1)") (class "Default")
      (node (ref "U4") (pin "1") (pinfunction "COFS/RG15_1") (pintype "passive"))
    )
    (net (code "89") (name "unconnected-(U4-CSCK{slash}RG14-Pad62)") (class "Default")
      (node (ref "U4") (pin "62") (pinfunction "CSCK/RG14_62") (pintype "passive"))
    )
    (net (code "90") (name "unconnected-(U4-CSDI{slash}RG12-Pad63)") (class "Default")
      (node (ref "U4") (pin "63") (pinfunction "CSDI/RG12_63") (pintype "passive"))
    )
    (net (code "91") (name "unconnected-(U4-CSDO{slash}RG13-Pad64)") (class "Default")
      (node (ref "U4") (pin "64") (pinfunction "CSDO/RG13_64") (pintype "passive"))
    )
    (net (code "92") (name "unconnected-(U4-EMUC3{slash}SCK1{slash}INT0{slash}RF6-Pad35)") (class "Default")
      (node (ref "U4") (pin "35") (pinfunction "EMUC3/SCK1/INT0/RF6_35") (pintype "passive"))
    )
    (net (code "93") (name "unconnected-(U4-SCK2{slash}CN8{slash}RG6-Pad4)") (class "Default")
      (node (ref "U4") (pin "4") (pinfunction "SCK2/CN8/RG6_4") (pintype "passive"))
    )
    (net (code "94") (name "unconnected-(U4-SDA{slash}RG3-Pad36)") (class "Default")
      (node (ref "U4") (pin "36") (pinfunction "SDA/RG3_36") (pintype "passive"))
    )
    (net (code "95") (name "unconnected-(U4-SDI2{slash}CN9{slash}RG7-Pad5)") (class "Default")
      (node (ref "U4") (pin "5") (pinfunction "SDI2/CN9/RG7_5") (pintype "passive"))
    )
    (net (code "96") (name "unconnected-(U4-SDO2{slash}CN10{slash}RG8-Pad6)") (class "Default")
      (node (ref "U4") (pin "6") (pinfunction "SDO2/CN10/RG8_6") (pintype "passive"))
    )
    (net (code "97") (name "unconnected-(U4-T2CK{slash}RC1-Pad2)") (class "Default")
      (node (ref "U4") (pin "2") (pinfunction "T2CK/RC1_2") (pintype "passive"))
    )
    (net (code "98") (name "unconnected-(U4-T3CK{slash}RC2-Pad3)") (class "Default")
      (node (ref "U4") (pin "3") (pinfunction "T3CK/RC2_3") (pintype "passive"))
    )
  )
)
